# fpga_gtp.net
KiCad netlist of a schematic drawn in Altium Designer
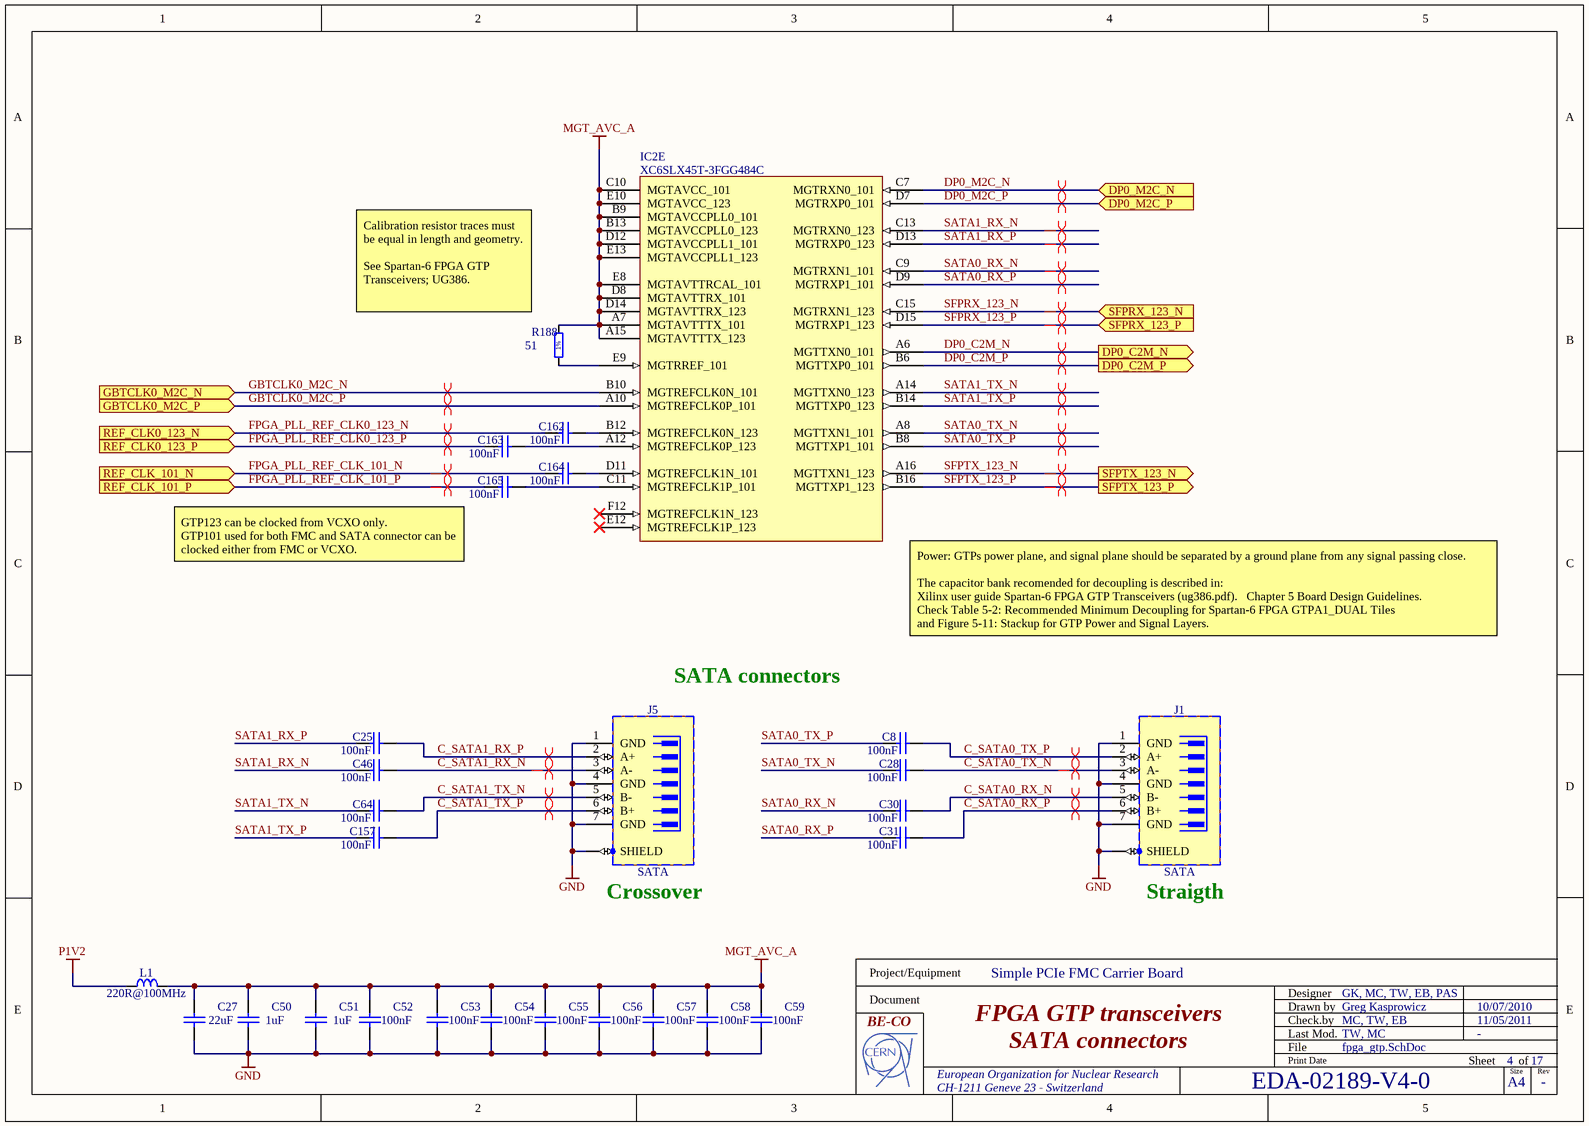
[diagram p0: fpga_gtp.SchDoc]

(export (version "E")
  (design (tool "Eeschema 10.0.6"))
  (components
    (comp (ref "C8")
      (value "100nF")
      (footprint "CAPC1005X55N")
      (description "Non-polarised capacitor")
      (fields
        (field (name "PART NUMBER") "CC0402_100NF_16V_10%_X7R")
        (field (name "VOLTAGE") "16V")
        (field (name "AUTHOR") "CERN DEM JLC")
      )
      (libsource (lib "Capacitors") (part "Capacitor - non polarized"))
    )
    (comp (ref "C25")
      (value "100nF")
      (footprint "CAPC1005X55N")
      (description "Non-polarised capacitor")
      (fields
        (field (name "PART NUMBER") "CC0402_100NF_16V_10%_X7R")
        (field (name "VOLTAGE") "16V")
        (field (name "AUTHOR") "CERN DEM JLC")
      )
      (libsource (lib "Capacitors") (part "Capacitor - non polarized"))
    )
    (comp (ref "C27")
      (value "22uF")
      (footprint "CAPC3216X180N")
      (description "Non-polarised capacitor")
      (fields
        (field (name "PART NUMBER") "CC1206_22UF_10V_10%_X7R")
        (field (name "VOLTAGE") "10V")
        (field (name "AUTHOR") "CERN DEM JLC")
      )
      (libsource (lib "Capacitors") (part "Capacitor - non polarized"))
    )
    (comp (ref "C28")
      (value "100nF")
      (footprint "CAPC1005X55N")
      (description "Non-polarised capacitor")
      (fields
        (field (name "PART NUMBER") "CC0402_100NF_16V_10%_X7R")
        (field (name "VOLTAGE") "16V")
        (field (name "AUTHOR") "CERN DEM JLC")
      )
      (libsource (lib "Capacitors") (part "Capacitor - non polarized"))
    )
    (comp (ref "C30")
      (value "100nF")
      (footprint "CAPC1005X55N")
      (description "Non-polarised capacitor")
      (fields
        (field (name "PART NUMBER") "CC0402_100NF_16V_10%_X7R")
        (field (name "VOLTAGE") "16V")
        (field (name "AUTHOR") "CERN DEM JLC")
      )
      (libsource (lib "Capacitors") (part "Capacitor - non polarized"))
    )
    (comp (ref "C31")
      (value "100nF")
      (footprint "CAPC1005X55N")
      (description "Non-polarised capacitor")
      (fields
        (field (name "PART NUMBER") "CC0402_100NF_16V_10%_X7R")
        (field (name "VOLTAGE") "16V")
        (field (name "AUTHOR") "CERN DEM JLC")
      )
      (libsource (lib "Capacitors") (part "Capacitor - non polarized"))
    )
    (comp (ref "C46")
      (value "100nF")
      (footprint "CAPC1005X55N")
      (description "Non-polarised capacitor")
      (fields
        (field (name "PART NUMBER") "CC0402_100NF_16V_10%_X7R")
        (field (name "VOLTAGE") "16V")
        (field (name "AUTHOR") "CERN DEM JLC")
      )
      (libsource (lib "Capacitors") (part "Capacitor - non polarized"))
    )
    (comp (ref "C50")
      (value "1uF")
      (footprint "CAPC1608X87N")
      (description "Non-polarised capacitor")
      (fields
        (field (name "PART NUMBER") "CC0603_1UF_16V_10%_X7R")
        (field (name "VOLTAGE") "16V")
        (field (name "AUTHOR") "CERN DEM JLC")
      )
      (libsource (lib "Capacitors") (part "Capacitor - non polarized"))
    )
    (comp (ref "C51")
      (value "1uF")
      (footprint "CAPC1608X87N")
      (description "Non-polarised capacitor")
      (fields
        (field (name "PART NUMBER") "CC0603_1UF_16V_10%_X7R")
        (field (name "VOLTAGE") "16V")
        (field (name "AUTHOR") "CERN DEM JLC")
      )
      (libsource (lib "Capacitors") (part "Capacitor - non polarized"))
    )
    (comp (ref "C52")
      (value "100nF")
      (footprint "CAPC1005X55N")
      (description "Non-polarised capacitor")
      (fields
        (field (name "PART NUMBER") "CC0402_100NF_16V_10%_X7R")
        (field (name "VOLTAGE") "16V")
        (field (name "AUTHOR") "CERN DEM JLC")
      )
      (libsource (lib "Capacitors") (part "Capacitor - non polarized"))
    )
    (comp (ref "C53")
      (value "100nF")
      (footprint "CAPC1005X55N")
      (description "Non-polarised capacitor")
      (fields
        (field (name "PART NUMBER") "CC0402_100NF_16V_10%_X7R")
        (field (name "VOLTAGE") "16V")
        (field (name "AUTHOR") "CERN DEM JLC")
      )
      (libsource (lib "Capacitors") (part "Capacitor - non polarized"))
    )
    (comp (ref "C54")
      (value "100nF")
      (footprint "CAPC1005X55N")
      (description "Non-polarised capacitor")
      (fields
        (field (name "PART NUMBER") "CC0402_100NF_16V_10%_X7R")
        (field (name "VOLTAGE") "16V")
        (field (name "AUTHOR") "CERN DEM JLC")
      )
      (libsource (lib "Capacitors") (part "Capacitor - non polarized"))
    )
    (comp (ref "C55")
      (value "100nF")
      (footprint "CAPC1005X55N")
      (description "Non-polarised capacitor")
      (fields
        (field (name "PART NUMBER") "CC0402_100NF_16V_10%_X7R")
        (field (name "VOLTAGE") "16V")
        (field (name "AUTHOR") "CERN DEM JLC")
      )
      (libsource (lib "Capacitors") (part "Capacitor - non polarized"))
    )
    (comp (ref "C56")
      (value "100nF")
      (footprint "CAPC1005X55N")
      (description "Non-polarised capacitor")
      (fields
        (field (name "PART NUMBER") "CC0402_100NF_16V_10%_X7R")
        (field (name "VOLTAGE") "16V")
        (field (name "AUTHOR") "CERN DEM JLC")
      )
      (libsource (lib "Capacitors") (part "Capacitor - non polarized"))
    )
    (comp (ref "C57")
      (value "100nF")
      (footprint "CAPC1005X55N")
      (description "Non-polarised capacitor")
      (fields
        (field (name "PART NUMBER") "CC0402_100NF_16V_10%_X7R")
        (field (name "VOLTAGE") "16V")
        (field (name "AUTHOR") "CERN DEM JLC")
      )
      (libsource (lib "Capacitors") (part "Capacitor - non polarized"))
    )
    (comp (ref "C58")
      (value "100nF")
      (footprint "CAPC1005X55N")
      (description "Non-polarised capacitor")
      (fields
        (field (name "PART NUMBER") "CC0402_100NF_16V_10%_X7R")
        (field (name "VOLTAGE") "16V")
        (field (name "AUTHOR") "CERN DEM JLC")
      )
      (libsource (lib "Capacitors") (part "Capacitor - non polarized"))
    )
    (comp (ref "C59")
      (value "100nF")
      (footprint "CAPC1005X55N")
      (description "Non-polarised capacitor")
      (fields
        (field (name "PART NUMBER") "CC0402_100NF_16V_10%_X7R")
        (field (name "VOLTAGE") "16V")
        (field (name "AUTHOR") "CERN DEM JLC")
      )
      (libsource (lib "Capacitors") (part "Capacitor - non polarized"))
    )
    (comp (ref "C64")
      (value "100nF")
      (footprint "CAPC1005X55N")
      (description "Non-polarised capacitor")
      (fields
        (field (name "PART NUMBER") "CC0402_100NF_16V_10%_X7R")
        (field (name "VOLTAGE") "16V")
        (field (name "AUTHOR") "CERN DEM JLC")
      )
      (libsource (lib "Capacitors") (part "Capacitor - non polarized"))
    )
    (comp (ref "C157")
      (value "100nF")
      (footprint "CAPC1005X55N")
      (description "Non-polarised capacitor")
      (fields
        (field (name "PART NUMBER") "CC0402_100NF_16V_10%_X7R")
        (field (name "VOLTAGE") "16V")
        (field (name "AUTHOR") "CERN DEM JLC")
      )
      (libsource (lib "Capacitors") (part "Capacitor - non polarized"))
    )
    (comp (ref "C162")
      (value "100nF")
      (footprint "CAPC1005X55N")
      (description "Non-polarised capacitor")
      (fields
        (field (name "PART NUMBER") "CC0402_100NF_16V_10%_X7R")
        (field (name "VOLTAGE") "16V")
        (field (name "AUTHOR") "CERN DEM JLC")
      )
      (libsource (lib "Capacitors") (part "Capacitor - non polarized"))
    )
    (comp (ref "C163")
      (value "100nF")
      (footprint "CAPC1005X55N")
      (description "Non-polarised capacitor")
      (fields
        (field (name "PART NUMBER") "CC0402_100NF_16V_10%_X7R")
        (field (name "VOLTAGE") "16V")
        (field (name "AUTHOR") "CERN DEM JLC")
      )
      (libsource (lib "Capacitors") (part "Capacitor - non polarized"))
    )
    (comp (ref "C164")
      (value "100nF")
      (footprint "CAPC1005X55N")
      (description "Non-polarised capacitor")
      (fields
        (field (name "PART NUMBER") "CC0402_100NF_16V_10%_X7R")
        (field (name "VOLTAGE") "16V")
        (field (name "AUTHOR") "CERN DEM JLC")
      )
      (libsource (lib "Capacitors") (part "Capacitor - non polarized"))
    )
    (comp (ref "C165")
      (value "100nF")
      (footprint "CAPC1005X55N")
      (description "Non-polarised capacitor")
      (fields
        (field (name "PART NUMBER") "CC0402_100NF_16V_10%_X7R")
        (field (name "VOLTAGE") "16V")
        (field (name "AUTHOR") "CERN DEM JLC")
      )
      (libsource (lib "Capacitors") (part "Capacitor - non polarized"))
    )
    (comp (ref "IC2")
      (value "XC6SLX45T-3FGG484C")
      (footprint "BGA484C100P22X22_2300X2300X260")
      (fields (field (name "MANUFACTURER") "XILINX") (field (name "AUTHOR") "CERN DEM JLC"))
      (libsource (lib "ICs And Semiconductors") (part "XC6SLX45T-3FGG484C"))
    )
    (comp (ref "J1")
      (value "SATA")
      (footprint "3M_5607-4200-SH")
      (description "7 Pin + 1 Shield SATA Receptacle")
      (fields
        (field (name "PART NUMBER") "3M_5607-4200-SH")
        (field (name "MANUFACTURER") "3M")
        (field (name "AUTHOR") "CERN DEM JLC")
      )
      (libsource (lib "Connectors") (part "Connector SATA 7 Male + 1 Shield"))
    )
    (comp (ref "J5")
      (value "SATA")
      (footprint "3M_5607-4200-SH")
      (description "7 Pin + 1 Shield SATA Receptacle")
      (fields
        (field (name "PART NUMBER") "3M_5607-4200-SH")
        (field (name "MANUFACTURER") "3M")
        (field (name "AUTHOR") "CERN DEM JLC")
      )
      (libsource (lib "Connectors") (part "Connector SATA 7 Male + 1 Shield"))
    )
    (comp (ref "L1")
      (value "220R@100MHz")
      (footprint "INDC2012X105N")
      (description "Inductor")
      (fields
        (field (name "PART NUMBER") "IND0805_MURATA_BLM21PG221SN1D")
        (field (name "POWER") "2A")
        (field (name "AUTHOR") "CERN DEM JLC")
      )
      (libsource (lib "Inductors & Transformers") (part "Inductor"))
    )
    (comp (ref "R188")
      (value "51")
      (footprint "RESC1005X40N")
      (description "Resistor - 1%")
      (fields
        (field (name "PART NUMBER") "R0402_51R_1%_0.0625W_100PPM")
        (field (name "POWER") "0.0625W")
        (field (name "AUTHOR") "CERN DEM JLC")
      )
      (libsource (lib "Resistors") (part "Resistor - 1%"))
    )
  )
  (nets
    (net (code "1") (name "/C_SATA0_RX_N") (class "Default")
      (node (ref "C30") (pin "2") (pinfunction "2_2") (pintype "passive"))
      (node (ref "J1") (pin "5") (pinfunction "B-_5") (pintype "bidirectional"))
    )
    (net (code "2") (name "/C_SATA0_RX_P") (class "Default")
      (node (ref "C31") (pin "2") (pinfunction "2_2") (pintype "passive"))
      (node (ref "J1") (pin "6") (pinfunction "B+_6") (pintype "bidirectional"))
    )
    (net (code "3") (name "/C_SATA0_TX_N") (class "Default")
      (node (ref "C28") (pin "2") (pinfunction "2_2") (pintype "passive"))
      (node (ref "J1") (pin "3") (pinfunction "A-_3") (pintype "bidirectional"))
    )
    (net (code "4") (name "/C_SATA0_TX_P") (class "Default")
      (node (ref "C8") (pin "2") (pinfunction "2_2") (pintype "passive"))
      (node (ref "J1") (pin "2") (pinfunction "A+_2") (pintype "bidirectional"))
    )
    (net (code "5") (name "/C_SATA1_RX_N") (class "Default")
      (node (ref "C46") (pin "2") (pinfunction "2_2") (pintype "passive"))
      (node (ref "J5") (pin "3") (pinfunction "A-_3") (pintype "bidirectional"))
    )
    (net (code "6") (name "/C_SATA1_RX_P") (class "Default")
      (node (ref "C25") (pin "2") (pinfunction "2_2") (pintype "passive"))
      (node (ref "J5") (pin "2") (pinfunction "A+_2") (pintype "bidirectional"))
    )
    (net (code "7") (name "/C_SATA1_TX_N") (class "Default")
      (node (ref "C64") (pin "2") (pinfunction "2_2") (pintype "passive"))
      (node (ref "J5") (pin "5") (pinfunction "B-_5") (pintype "bidirectional"))
    )
    (net (code "8") (name "/C_SATA1_TX_P") (class "Default")
      (node (ref "C157") (pin "2") (pinfunction "2_2") (pintype "passive"))
      (node (ref "J5") (pin "6") (pinfunction "B+_6") (pintype "bidirectional"))
    )
    (net (code "9") (name "/DP0_C2M_N") (class "Default")
      (node (ref "IC2") (pin "A6") (pinfunction "MGTTXN0_101_A6") (pintype "output"))
    )
    (net (code "10") (name "/DP0_C2M_P") (class "Default")
      (node (ref "IC2") (pin "B6") (pinfunction "MGTTXP0_101_B6") (pintype "output"))
    )
    (net (code "11") (name "/DP0_M2C_N") (class "Default")
      (node (ref "IC2") (pin "C7") (pinfunction "MGTRXN0_101_C7") (pintype "input"))
    )
    (net (code "12") (name "/DP0_M2C_P") (class "Default")
      (node (ref "IC2") (pin "D7") (pinfunction "MGTRXP0_101_D7") (pintype "input"))
    )
    (net (code "13") (name "/FPGA_PLL_REF_CLK0_123_N") (class "Default")
      (node (ref "C162") (pin "1") (pinfunction "1_1") (pintype "passive"))
    )
    (net (code "14") (name "/FPGA_PLL_REF_CLK0_123_P") (class "Default")
      (node (ref "C163") (pin "1") (pinfunction "1_1") (pintype "passive"))
    )
    (net (code "15") (name "/FPGA_PLL_REF_CLK_101_N") (class "Default")
      (node (ref "C164") (pin "1") (pinfunction "1_1") (pintype "passive"))
    )
    (net (code "16") (name "/FPGA_PLL_REF_CLK_101_P") (class "Default")
      (node (ref "C165") (pin "1") (pinfunction "1_1") (pintype "passive"))
    )
    (net (code "17") (name "/GBTCLK0_M2C_N") (class "Default")
      (node (ref "IC2") (pin "B10") (pinfunction "MGTREFCLK0N_101_B10") (pintype "input"))
    )
    (net (code "18") (name "/GBTCLK0_M2C_P") (class "Default")
      (node (ref "IC2") (pin "A10") (pinfunction "MGTREFCLK0P_101_A10") (pintype "input"))
    )
    (net (code "19") (name "/SATA0_RX_N") (class "Default")
      (node (ref "C30") (pin "1") (pinfunction "1_1") (pintype "passive"))
      (node (ref "IC2") (pin "C9") (pinfunction "MGTRXN1_101_C9") (pintype "input"))
    )
    (net (code "20") (name "/SATA0_RX_P") (class "Default")
      (node (ref "C31") (pin "1") (pinfunction "1_1") (pintype "passive"))
      (node (ref "IC2") (pin "D9") (pinfunction "MGTRXP1_101_D9") (pintype "input"))
    )
    (net (code "21") (name "/SATA0_TX_N") (class "Default")
      (node (ref "C28") (pin "1") (pinfunction "1_1") (pintype "passive"))
      (node (ref "IC2") (pin "A8") (pinfunction "MGTTXN1_101_A8") (pintype "output"))
    )
    (net (code "22") (name "/SATA0_TX_P") (class "Default")
      (node (ref "C8") (pin "1") (pinfunction "1_1") (pintype "passive"))
      (node (ref "IC2") (pin "B8") (pinfunction "MGTTXP1_101_B8") (pintype "output"))
    )
    (net (code "23") (name "/SATA1_RX_N") (class "Default")
      (node (ref "C46") (pin "1") (pinfunction "1_1") (pintype "passive"))
      (node (ref "IC2") (pin "C13") (pinfunction "MGTRXN0_123_C13") (pintype "input"))
    )
    (net (code "24") (name "/SATA1_RX_P") (class "Default")
      (node (ref "C25") (pin "1") (pinfunction "1_1") (pintype "passive"))
      (node (ref "IC2") (pin "D13") (pinfunction "MGTRXP0_123_D13") (pintype "input"))
    )
    (net (code "25") (name "/SATA1_TX_N") (class "Default")
      (node (ref "C64") (pin "1") (pinfunction "1_1") (pintype "passive"))
      (node (ref "IC2") (pin "A14") (pinfunction "MGTTXN0_123_A14") (pintype "output"))
    )
    (net (code "26") (name "/SATA1_TX_P") (class "Default")
      (node (ref "C157") (pin "1") (pinfunction "1_1") (pintype "passive"))
      (node (ref "IC2") (pin "B14") (pinfunction "MGTTXP0_123_B14") (pintype "output"))
    )
    (net (code "27") (name "/SFPRX_123_N") (class "Default")
      (node (ref "IC2") (pin "C15") (pinfunction "MGTRXN1_123_C15") (pintype "input"))
    )
    (net (code "28") (name "/SFPRX_123_P") (class "Default")
      (node (ref "IC2") (pin "D15") (pinfunction "MGTRXP1_123_D15") (pintype "input"))
    )
    (net (code "29") (name "/SFPTX_123_N") (class "Default")
      (node (ref "IC2") (pin "A16") (pinfunction "MGTTXN1_123_A16") (pintype "output"))
    )
    (net (code "30") (name "/SFPTX_123_P") (class "Default")
      (node (ref "IC2") (pin "B16") (pinfunction "MGTTXP1_123_B16") (pintype "output"))
    )
    (net (code "31") (name "GND") (class "Default")
      (node (ref "C27") (pin "1") (pinfunction "1_1") (pintype "passive"))
      (node (ref "C50") (pin "1") (pinfunction "1_1") (pintype "passive"))
      (node (ref "C51") (pin "1") (pinfunction "1_1") (pintype "passive"))
      (node (ref "C52") (pin "1") (pinfunction "1_1") (pintype "passive"))
      (node (ref "C53") (pin "1") (pinfunction "1_1") (pintype "passive"))
      (node (ref "C54") (pin "1") (pinfunction "1_1") (pintype "passive"))
      (node (ref "C55") (pin "1") (pinfunction "1_1") (pintype "passive"))
      (node (ref "C56") (pin "1") (pinfunction "1_1") (pintype "passive"))
      (node (ref "C57") (pin "1") (pinfunction "1_1") (pintype "passive"))
      (node (ref "C58") (pin "1") (pinfunction "1_1") (pintype "passive"))
      (node (ref "C59") (pin "1") (pinfunction "1_1") (pintype "passive"))
      (node (ref "J1") (pin "1") (pinfunction "GND_1") (pintype "power_in"))
      (node (ref "J1") (pin "4") (pinfunction "GND_4") (pintype "power_in"))
      (node (ref "J1") (pin "7") (pinfunction "GND_7") (pintype "power_in"))
      (node (ref "J1") (pin "8") (pinfunction "SHIELD_8") (pintype "bidirectional"))
      (node (ref "J5") (pin "1") (pinfunction "GND_1") (pintype "power_in"))
      (node (ref "J5") (pin "4") (pinfunction "GND_4") (pintype "power_in"))
      (node (ref "J5") (pin "7") (pinfunction "GND_7") (pintype "power_in"))
      (node (ref "J5") (pin "8") (pinfunction "SHIELD_8") (pintype "bidirectional"))
    )
    (net (code "32") (name "MGT_AVC_A") (class "Default")
      (node (ref "C27") (pin "2") (pinfunction "2_2") (pintype "passive"))
      (node (ref "C50") (pin "2") (pinfunction "2_2") (pintype "passive"))
      (node (ref "C51") (pin "2") (pinfunction "2_2") (pintype "passive"))
      (node (ref "C52") (pin "2") (pinfunction "2_2") (pintype "passive"))
      (node (ref "C53") (pin "2") (pinfunction "2_2") (pintype "passive"))
      (node (ref "C54") (pin "2") (pinfunction "2_2") (pintype "passive"))
      (node (ref "C55") (pin "2") (pinfunction "2_2") (pintype "passive"))
      (node (ref "C56") (pin "2") (pinfunction "2_2") (pintype "passive"))
      (node (ref "C57") (pin "2") (pinfunction "2_2") (pintype "passive"))
      (node (ref "C58") (pin "2") (pinfunction "2_2") (pintype "passive"))
      (node (ref "C59") (pin "2") (pinfunction "2_2") (pintype "passive"))
      (node (ref "IC2") (pin "A15") (pinfunction "MGTAVTTTX_123_A15") (pintype "power_in"))
      (node (ref "IC2") (pin "A7") (pinfunction "MGTAVTTTX_101_A7") (pintype "power_in"))
      (node (ref "IC2") (pin "B13") (pinfunction "MGTAVCCPLL0_123_B13") (pintype "power_in"))
      (node (ref "IC2") (pin "B9") (pinfunction "MGTAVCCPLL0_101_B9") (pintype "power_in"))
      (node (ref "IC2") (pin "C10") (pinfunction "MGTAVCC_101_C10") (pintype "power_in"))
      (node (ref "IC2") (pin "D12") (pinfunction "MGTAVCCPLL1_101_D12") (pintype "power_in"))
      (node (ref "IC2") (pin "D14") (pinfunction "MGTAVTTRX_123_D14") (pintype "power_in"))
      (node (ref "IC2") (pin "D8") (pinfunction "MGTAVTTRX_101_D8") (pintype "power_in"))
      (node (ref "IC2") (pin "E10") (pinfunction "MGTAVCC_123_E10") (pintype "power_in"))
      (node (ref "IC2") (pin "E13") (pinfunction "MGTAVCCPLL1_123_E13") (pintype "power_in"))
      (node (ref "IC2") (pin "E8") (pinfunction "MGTAVTTRCAL_101_E8") (pintype "power_in"))
      (node (ref "L1") (pin "2") (pinfunction "2_2") (pintype "passive"))
      (node (ref "R188") (pin "2") (pinfunction "2_2") (pintype "passive"))
    )
    (net (code "33") (name "Net-(IC2E-MGTREFCLK0N_123)") (class "Default")
      (node (ref "C162") (pin "2") (pinfunction "2_2") (pintype "passive"))
      (node (ref "IC2") (pin "B12") (pinfunction "MGTREFCLK0N_123_B12") (pintype "input"))
    )
    (net (code "34") (name "Net-(IC2E-MGTREFCLK0P_123)") (class "Default")
      (node (ref "C163") (pin "2") (pinfunction "2_2") (pintype "passive"))
      (node (ref "IC2") (pin "A12") (pinfunction "MGTREFCLK0P_123_A12") (pintype "input"))
    )
    (net (code "35") (name "Net-(IC2E-MGTREFCLK1N_101)") (class "Default")
      (node (ref "C164") (pin "2") (pinfunction "2_2") (pintype "passive"))
      (node (ref "IC2") (pin "D11") (pinfunction "MGTREFCLK1N_101_D11") (pintype "input"))
    )
    (net (code "36") (name "Net-(IC2E-MGTREFCLK1P_101)") (class "Default")
      (node (ref "C165") (pin "2") (pinfunction "2_2") (pintype "passive"))
      (node (ref "IC2") (pin "C11") (pinfunction "MGTREFCLK1P_101_C11") (pintype "input"))
    )
    (net (code "37") (name "Net-(IC2E-MGTRREF_101)") (class "Default")
      (node (ref "IC2") (pin "E9") (pinfunction "MGTRREF_101_E9") (pintype "input"))
      (node (ref "R188") (pin "1") (pinfunction "1_1") (pintype "passive"))
    )
    (net (code "38") (name "P1V2") (class "Default")
      (node (ref "L1") (pin "1") (pinfunction "1_1") (pintype "passive"))
    )
    (net (code "39") (name "unconnected-(IC2E-MGTREFCLK1N_123-PadF12)") (class "Default")
      (node (ref "IC2") (pin "F12") (pinfunction "MGTREFCLK1N_123_F12") (pintype "input+no_connect"))
    )
    (net (code "40") (name "unconnected-(IC2E-MGTREFCLK1P_123-PadE12)") (class "Default")
      (node (ref "IC2") (pin "E12") (pinfunction "MGTREFCLK1P_123_E12") (pintype "input+no_connect"))
    )
  )
)
